# 03-MCU.net
KiCad netlist of a schematic drawn in Altium Designer
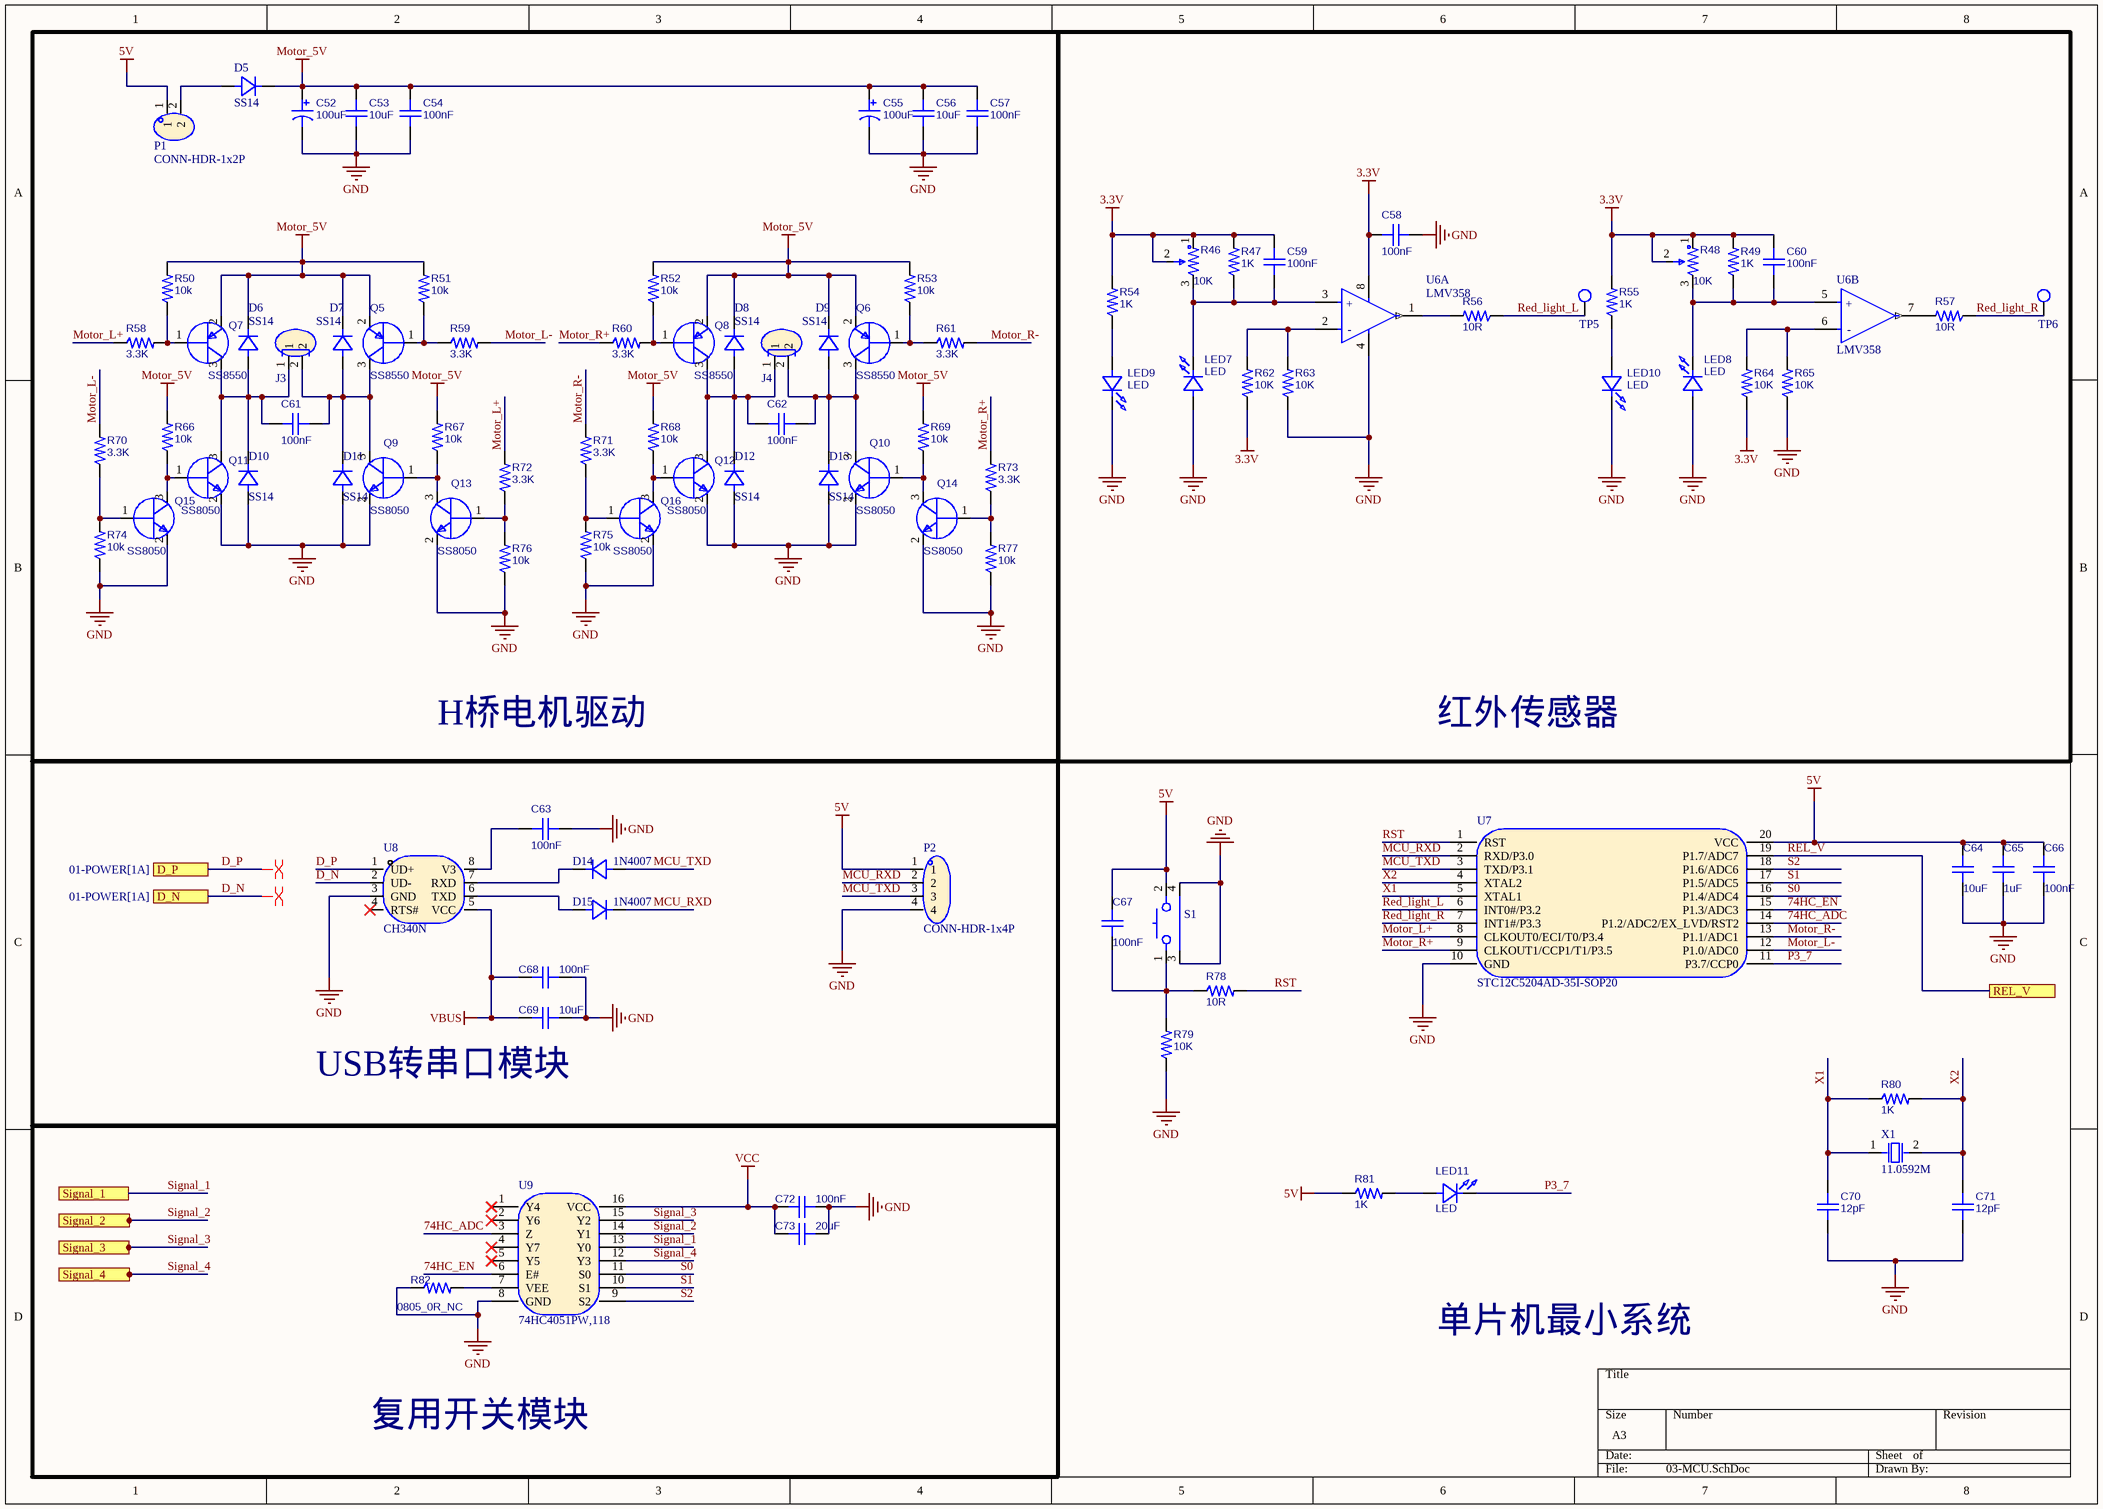
[diagram p0: 03-MCU.SchDoc]

(export (version "E")
  (design (tool "Eeschema 10.0.6"))
  (components
    (comp (ref "C52")
      (value "100uF")
      (footprint "CAPA-TH-5020-P2.0")
      (description "电解电容")
      (fields
        (field (name "BOM_MANUFACTURER PART") "普通黑色470UF 50V")
        (field (name "BOM_SUPPLIER PART") "C34642")
      )
      (libsource (lib "声源跟踪小车原理图库") (part "CAPA"))
    )
    (comp (ref "C53")
      (value "10uF")
      (footprint "CAP-SMD-0603")
      (description "贴片电容")
      (fields
        (field (name "BOM_MANUFACTURER PART") "CL03A104KQ3NNNC")
        (field (name "BOM_SUPPLIER PART") "C160831")
        (field (name "CONTRIBUTOR") "LCSC")
      )
      (libsource (lib "声源跟踪小车原理图库") (part "CAP"))
    )
    (comp (ref "C54")
      (value "100nF")
      (footprint "CAP-SMD-0603")
      (description "贴片电容")
      (fields
        (field (name "BOM_MANUFACTURER PART") "CL03A104KQ3NNNC")
        (field (name "BOM_SUPPLIER PART") "C160831")
        (field (name "CONTRIBUTOR") "LCSC")
      )
      (libsource (lib "声源跟踪小车原理图库") (part "CAP"))
    )
    (comp (ref "C55")
      (value "100uF")
      (footprint "CAPA-TH-5020-P2.0")
      (description "电解电容")
      (fields
        (field (name "BOM_MANUFACTURER PART") "普通黑色470UF 50V")
        (field (name "BOM_SUPPLIER PART") "C34642")
      )
      (libsource (lib "声源跟踪小车原理图库") (part "CAPA"))
    )
    (comp (ref "C56")
      (value "10uF")
      (footprint "CAP-SMD-0603")
      (description "贴片电容")
      (fields
        (field (name "BOM_MANUFACTURER PART") "CL03A104KQ3NNNC")
        (field (name "BOM_SUPPLIER PART") "C160831")
        (field (name "CONTRIBUTOR") "LCSC")
      )
      (libsource (lib "声源跟踪小车原理图库") (part "CAP"))
    )
    (comp (ref "C57")
      (value "100nF")
      (footprint "CAP-SMD-0603")
      (description "贴片电容")
      (fields
        (field (name "BOM_MANUFACTURER PART") "CL03A104KQ3NNNC")
        (field (name "BOM_SUPPLIER PART") "C160831")
        (field (name "CONTRIBUTOR") "LCSC")
      )
      (libsource (lib "声源跟踪小车原理图库") (part "CAP"))
    )
    (comp (ref "C58")
      (value "100nF")
      (footprint "CAP-SMD-0603")
      (description "贴片电容")
      (fields
        (field (name "BOM_MANUFACTURER PART") "CL03A104KQ3NNNC")
        (field (name "BOM_SUPPLIER PART") "C160831")
        (field (name "CONTRIBUTOR") "LCSC")
      )
      (libsource (lib "声源跟踪小车原理图库") (part "CAP"))
    )
    (comp (ref "C59")
      (value "100nF")
      (footprint "CAP-SMD-0603")
      (description "贴片电容")
      (fields
        (field (name "BOM_MANUFACTURER PART") "CL03A104KQ3NNNC")
        (field (name "BOM_SUPPLIER PART") "C160831")
        (field (name "CONTRIBUTOR") "LCSC")
      )
      (libsource (lib "声源跟踪小车原理图库") (part "CAP"))
    )
    (comp (ref "C60")
      (value "100nF")
      (footprint "CAP-SMD-0603")
      (description "贴片电容")
      (fields
        (field (name "BOM_MANUFACTURER PART") "CL03A104KQ3NNNC")
        (field (name "BOM_SUPPLIER PART") "C160831")
        (field (name "CONTRIBUTOR") "LCSC")
      )
      (libsource (lib "声源跟踪小车原理图库") (part "CAP"))
    )
    (comp (ref "C61")
      (value "100nF")
      (footprint "CAP-SMD-0603")
      (description "贴片电容")
      (fields
        (field (name "BOM_MANUFACTURER PART") "CL03A104KQ3NNNC")
        (field (name "BOM_SUPPLIER PART") "C160831")
        (field (name "CONTRIBUTOR") "LCSC")
      )
      (libsource (lib "声源跟踪小车原理图库") (part "CAP"))
    )
    (comp (ref "C62")
      (value "100nF")
      (footprint "CAP-SMD-0603")
      (description "贴片电容")
      (fields
        (field (name "BOM_MANUFACTURER PART") "CL03A104KQ3NNNC")
        (field (name "BOM_SUPPLIER PART") "C160831")
        (field (name "CONTRIBUTOR") "LCSC")
      )
      (libsource (lib "声源跟踪小车原理图库") (part "CAP"))
    )
    (comp (ref "C63")
      (value "100nF")
      (footprint "CAP-SMD-0603")
      (description "贴片电容")
      (fields
        (field (name "BOM_MANUFACTURER PART") "CL03A104KQ3NNNC")
        (field (name "BOM_SUPPLIER PART") "C160831")
        (field (name "CONTRIBUTOR") "LCSC")
      )
      (libsource (lib "声源跟踪小车原理图库") (part "CAP"))
    )
    (comp (ref "C64")
      (value "10uF")
      (footprint "CAP-SMD-0603")
      (description "贴片电容")
      (fields
        (field (name "BOM_MANUFACTURER PART") "CL03A104KQ3NNNC")
        (field (name "BOM_SUPPLIER PART") "C160831")
        (field (name "CONTRIBUTOR") "LCSC")
      )
      (libsource (lib "声源跟踪小车原理图库") (part "CAP"))
    )
    (comp (ref "C65")
      (value "1uF")
      (footprint "CAP-SMD-0603")
      (description "贴片电容")
      (fields
        (field (name "BOM_MANUFACTURER PART") "CL03A104KQ3NNNC")
        (field (name "BOM_SUPPLIER PART") "C160831")
        (field (name "CONTRIBUTOR") "LCSC")
      )
      (libsource (lib "声源跟踪小车原理图库") (part "CAP"))
    )
    (comp (ref "C66")
      (value "100nF")
      (footprint "CAP-SMD-0603")
      (description "贴片电容")
      (fields
        (field (name "BOM_MANUFACTURER PART") "CL03A104KQ3NNNC")
        (field (name "BOM_SUPPLIER PART") "C160831")
        (field (name "CONTRIBUTOR") "LCSC")
      )
      (libsource (lib "声源跟踪小车原理图库") (part "CAP"))
    )
    (comp (ref "C67")
      (value "100nF")
      (footprint "CAP-SMD-0603")
      (description "贴片电容")
      (fields
        (field (name "BOM_MANUFACTURER PART") "CL03A104KQ3NNNC")
        (field (name "BOM_SUPPLIER PART") "C160831")
        (field (name "CONTRIBUTOR") "LCSC")
      )
      (libsource (lib "声源跟踪小车原理图库") (part "CAP"))
    )
    (comp (ref "C68")
      (value "100nF")
      (footprint "CAP-SMD-0603")
      (description "贴片电容")
      (fields
        (field (name "BOM_MANUFACTURER PART") "CL03A104KQ3NNNC")
        (field (name "BOM_SUPPLIER PART") "C160831")
        (field (name "CONTRIBUTOR") "LCSC")
      )
      (libsource (lib "声源跟踪小车原理图库") (part "CAP"))
    )
    (comp (ref "C69")
      (value "10uF")
      (footprint "CAP-SMD-0603")
      (description "贴片电容")
      (fields
        (field (name "BOM_MANUFACTURER PART") "CL03A104KQ3NNNC")
        (field (name "BOM_SUPPLIER PART") "C160831")
        (field (name "CONTRIBUTOR") "LCSC")
      )
      (libsource (lib "声源跟踪小车原理图库") (part "CAP"))
    )
    (comp (ref "C70")
      (value "12pF")
      (footprint "CAP-SMD-0603")
      (description "贴片电容")
      (fields
        (field (name "BOM_MANUFACTURER PART") "CL03A104KQ3NNNC")
        (field (name "BOM_SUPPLIER PART") "C160831")
        (field (name "CONTRIBUTOR") "LCSC")
      )
      (libsource (lib "声源跟踪小车原理图库") (part "CAP"))
    )
    (comp (ref "C71")
      (value "12pF")
      (footprint "CAP-SMD-0603")
      (description "贴片电容")
      (fields
        (field (name "BOM_MANUFACTURER PART") "CL03A104KQ3NNNC")
        (field (name "BOM_SUPPLIER PART") "C160831")
        (field (name "CONTRIBUTOR") "LCSC")
      )
      (libsource (lib "声源跟踪小车原理图库") (part "CAP"))
    )
    (comp (ref "C72")
      (value "100nF")
      (footprint "CAP-SMD-0603")
      (description "贴片电容")
      (fields
        (field (name "BOM_MANUFACTURER PART") "CL03A104KQ3NNNC")
        (field (name "BOM_SUPPLIER PART") "C160831")
        (field (name "CONTRIBUTOR") "LCSC")
      )
      (libsource (lib "声源跟踪小车原理图库") (part "CAP"))
    )
    (comp (ref "C73")
      (value "20uF")
      (footprint "CAP-SMD-0603")
      (description "贴片电容")
      (fields
        (field (name "BOM_MANUFACTURER PART") "CL03A104KQ3NNNC")
        (field (name "BOM_SUPPLIER PART") "C160831")
        (field (name "CONTRIBUTOR") "LCSC")
      )
      (libsource (lib "声源跟踪小车原理图库") (part "CAP"))
    )
    (comp (ref "D5")
      (value "SS14")
      (footprint "SOD-123-P3.4")
      (description "二极管1N4148W")
      (fields (field (name "MANUFACTURER") "PSI(宝力芯)") (field (name "MANUFACTURER PART") "1N4148W"))
      (libsource (lib "声源跟踪小车原理图库") (part "Diode"))
    )
    (comp (ref "D6")
      (value "SS14")
      (footprint "SOD-123-P3.4")
      (description "二极管1N4148W")
      (fields (field (name "MANUFACTURER") "PSI(宝力芯)") (field (name "MANUFACTURER PART") "1N4148W"))
      (libsource (lib "声源跟踪小车原理图库") (part "Diode"))
    )
    (comp (ref "D7")
      (value "SS14")
      (footprint "SOD-123-P3.4")
      (description "二极管1N4148W")
      (fields (field (name "MANUFACTURER") "PSI(宝力芯)") (field (name "MANUFACTURER PART") "1N4148W"))
      (libsource (lib "声源跟踪小车原理图库") (part "Diode"))
    )
    (comp (ref "D8")
      (value "SS14")
      (footprint "SOD-123-P3.4")
      (description "二极管1N4148W")
      (fields (field (name "MANUFACTURER") "PSI(宝力芯)") (field (name "MANUFACTURER PART") "1N4148W"))
      (libsource (lib "声源跟踪小车原理图库") (part "Diode"))
    )
    (comp (ref "D9")
      (value "SS14")
      (footprint "SOD-123-P3.4")
      (description "二极管1N4148W")
      (fields (field (name "MANUFACTURER") "PSI(宝力芯)") (field (name "MANUFACTURER PART") "1N4148W"))
      (libsource (lib "声源跟踪小车原理图库") (part "Diode"))
    )
    (comp (ref "D10")
      (value "SS14")
      (footprint "SOD-123-P3.4")
      (description "二极管1N4148W")
      (fields (field (name "MANUFACTURER") "PSI(宝力芯)") (field (name "MANUFACTURER PART") "1N4148W"))
      (libsource (lib "声源跟踪小车原理图库") (part "Diode"))
    )
    (comp (ref "D11")
      (value "SS14")
      (footprint "SOD-123-P3.4")
      (description "二极管1N4148W")
      (fields (field (name "MANUFACTURER") "PSI(宝力芯)") (field (name "MANUFACTURER PART") "1N4148W"))
      (libsource (lib "声源跟踪小车原理图库") (part "Diode"))
    )
    (comp (ref "D12")
      (value "SS14")
      (footprint "SOD-123-P3.4")
      (description "二极管1N4148W")
      (fields (field (name "MANUFACTURER") "PSI(宝力芯)") (field (name "MANUFACTURER PART") "1N4148W"))
      (libsource (lib "声源跟踪小车原理图库") (part "Diode"))
    )
    (comp (ref "D13")
      (value "SS14")
      (footprint "SOD-123-P3.4")
      (description "二极管1N4148W")
      (fields (field (name "MANUFACTURER") "PSI(宝力芯)") (field (name "MANUFACTURER PART") "1N4148W"))
      (libsource (lib "声源跟踪小车原理图库") (part "Diode"))
    )
    (comp (ref "D14")
      (value "1N4007")
      (footprint "SOD-123-P3.4")
      (description "二极管1N4148W")
      (fields (field (name "MANUFACTURER") "PSI(宝力芯)") (field (name "MANUFACTURER PART") "1N4148W"))
      (libsource (lib "声源跟踪小车原理图库") (part "Diode"))
    )
    (comp (ref "D15")
      (value "1N4007")
      (footprint "SOD-123-P3.4")
      (description "二极管1N4148W")
      (fields (field (name "MANUFACTURER") "PSI(宝力芯)") (field (name "MANUFACTURER PART") "1N4148W"))
      (libsource (lib "声源跟踪小车原理图库") (part "Diode"))
    )
    (comp (ref "J3")
      (value "CONN-2P")
      (footprint "CONN-TH-CDS-1x2P-P2.54")
      (description "连接插座2pin")
      (fields (field (name "MANUFACTURER") "KEFA(科发)") (field (name "MANUFACTURER PART") "KF301-5.0-2P"))
      (libsource (lib "声源跟踪小车原理图库") (part "CONN-2P"))
    )
    (comp (ref "J4")
      (value "CONN-2P")
      (footprint "CONN-TH-CDS-1x2P-P2.54")
      (description "连接插座2pin")
      (fields (field (name "MANUFACTURER") "KEFA(科发)") (field (name "MANUFACTURER PART") "KF301-5.0-2P"))
      (libsource (lib "声源跟踪小车原理图库") (part "CONN-2P"))
    )
    (comp (ref "LED7")
      (value "LED")
      (footprint "LED-TH-D5.0-P2.54")
      (description "LED灯,发光二极管")
      (fields
        (field (name "BOM_SUPPLIER PART") "C434447")
        (field (name "BOM_MANUFACTURER PART") "SZYY0402B")
        (field (name "CONTRIBUTOR") "LCSC")
      )
      (libsource (lib "声源跟踪小车原理图库") (part "LED"))
    )
    (comp (ref "LED8")
      (value "LED")
      (footprint "LED-TH-D5.0-P2.54")
      (description "LED灯,发光二极管")
      (fields
        (field (name "BOM_SUPPLIER PART") "C434447")
        (field (name "BOM_MANUFACTURER PART") "SZYY0402B")
        (field (name "CONTRIBUTOR") "LCSC")
      )
      (libsource (lib "声源跟踪小车原理图库") (part "LED"))
    )
    (comp (ref "LED9")
      (value "LED")
      (footprint "LED-TH-D5.0-P2.54")
      (description "LED灯,发光二极管")
      (fields
        (field (name "BOM_SUPPLIER PART") "C434447")
        (field (name "BOM_MANUFACTURER PART") "SZYY0402B")
        (field (name "CONTRIBUTOR") "LCSC")
      )
      (libsource (lib "声源跟踪小车原理图库") (part "LED"))
    )
    (comp (ref "LED10")
      (value "LED")
      (footprint "LED-TH-D5.0-P2.54")
      (description "LED灯,发光二极管")
      (fields
        (field (name "BOM_SUPPLIER PART") "C434447")
        (field (name "BOM_MANUFACTURER PART") "SZYY0402B")
        (field (name "CONTRIBUTOR") "LCSC")
      )
      (libsource (lib "声源跟踪小车原理图库") (part "LED"))
    )
    (comp (ref "LED11")
      (value "LED")
      (footprint "LED-SMD-0805")
      (description "LED灯,发光二极管")
      (fields
        (field (name "BOM_SUPPLIER PART") "C434447")
        (field (name "BOM_MANUFACTURER PART") "SZYY0402B")
        (field (name "CONTRIBUTOR") "LCSC")
      )
      (libsource (lib "声源跟踪小车原理图库") (part "LED"))
    )
    (comp (ref "P1")
      (value "CONN-HDR-1x2P")
      (footprint "CONN-TH-1X2P-P2.54")
      (description "排针1*2pin")
      (fields
        (field (name "MANUFACTURER") "kinghelm(金航标)")
        (field (name "MANUFACTURER PART") "KH-2.54PH180-1X2P-L11.5")
      )
      (libsource (lib "声源跟踪小车原理图库") (part "CONN-HDR-1x2P"))
    )
    (comp (ref "P2")
      (value "CONN-HDR-1x4P")
      (footprint "CONN-TH-1X4P-P2.54")
      (description "排针1*4pin")
      (fields
        (field (name "MANUFACTURER") "Wcon(维峰电子)")
        (field (name "MANUFACTURER PART") "1125-1104G0S116C001")
      )
      (libsource (lib "声源跟踪小车原理图库") (part "CONN-HDR-1x4P"))
    )
    (comp (ref "Q5")
      (value "SS8550")
      (footprint "SOT-23-3-LP2.28-P1.91")
      (description "贴片PNP三极管")
      (fields
        (field (name "BOM_SUPPLIER PART") "C2891799")
        (field (name "BOM_MANUFACTURER PART") "S9012")
        (field (name "CONTRIBUTOR") "LCSC")
      )
      (libsource (lib "声源跟踪小车原理图库") (part "PNP-SOT-23-3"))
    )
    (comp (ref "Q6")
      (value "SS8550")
      (footprint "SOT-23-3-LP2.28-P1.91")
      (description "贴片PNP三极管")
      (fields
        (field (name "BOM_SUPPLIER PART") "C2891799")
        (field (name "BOM_MANUFACTURER PART") "S9012")
        (field (name "CONTRIBUTOR") "LCSC")
      )
      (libsource (lib "声源跟踪小车原理图库") (part "PNP-SOT-23-3"))
    )
    (comp (ref "Q7")
      (value "SS8550")
      (footprint "SOT-23-3-LP2.28-P1.91")
      (description "贴片PNP三极管")
      (fields
        (field (name "BOM_SUPPLIER PART") "C2891799")
        (field (name "BOM_MANUFACTURER PART") "S9012")
        (field (name "CONTRIBUTOR") "LCSC")
      )
      (libsource (lib "声源跟踪小车原理图库") (part "PNP-SOT-23-3"))
    )
    (comp (ref "Q8")
      (value "SS8550")
      (footprint "SOT-23-3-LP2.28-P1.91")
      (description "贴片PNP三极管")
      (fields
        (field (name "BOM_SUPPLIER PART") "C2891799")
        (field (name "BOM_MANUFACTURER PART") "S9012")
        (field (name "CONTRIBUTOR") "LCSC")
      )
      (libsource (lib "声源跟踪小车原理图库") (part "PNP-SOT-23-3"))
    )
    (comp (ref "Q9")
      (value "SS8050")
      (footprint "SOT-23-3-LP2.28-P1.91")
      (description "贴片NPN三极管")
      (fields
        (field (name "BOM_SUPPLIER PART") "C2898668")
        (field (name "BOM_MANUFACTURER PART") "S9013")
        (field (name "CONTRIBUTOR") "LCSC")
      )
      (libsource (lib "声源跟踪小车原理图库") (part "NPN-SOT-23-3"))
    )
    (comp (ref "Q10")
      (value "SS8050")
      (footprint "SOT-23-3-LP2.28-P1.91")
      (description "贴片NPN三极管")
      (fields
        (field (name "BOM_SUPPLIER PART") "C2898668")
        (field (name "BOM_MANUFACTURER PART") "S9013")
        (field (name "CONTRIBUTOR") "LCSC")
      )
      (libsource (lib "声源跟踪小车原理图库") (part "NPN-SOT-23-3"))
    )
    (comp (ref "Q11")
      (value "SS8050")
      (footprint "SOT-23-3-LP2.28-P1.91")
      (description "贴片NPN三极管")
      (fields
        (field (name "BOM_SUPPLIER PART") "C2898668")
        (field (name "BOM_MANUFACTURER PART") "S9013")
        (field (name "CONTRIBUTOR") "LCSC")
      )
      (libsource (lib "声源跟踪小车原理图库") (part "NPN-SOT-23-3"))
    )
    (comp (ref "Q12")
      (value "SS8050")
      (footprint "SOT-23-3-LP2.28-P1.91")
      (description "贴片NPN三极管")
      (fields
        (field (name "BOM_SUPPLIER PART") "C2898668")
        (field (name "BOM_MANUFACTURER PART") "S9013")
        (field (name "CONTRIBUTOR") "LCSC")
      )
      (libsource (lib "声源跟踪小车原理图库") (part "NPN-SOT-23-3"))
    )
    (comp (ref "Q13")
      (value "SS8050")
      (footprint "SOT-23-3-LP2.28-P1.91")
      (description "贴片NPN三极管")
      (fields
        (field (name "BOM_SUPPLIER PART") "C2898668")
        (field (name "BOM_MANUFACTURER PART") "S9013")
        (field (name "CONTRIBUTOR") "LCSC")
      )
      (libsource (lib "声源跟踪小车原理图库") (part "NPN-SOT-23-3"))
    )
    (comp (ref "Q14")
      (value "SS8050")
      (footprint "SOT-23-3-LP2.28-P1.91")
      (description "贴片NPN三极管")
      (fields
        (field (name "BOM_SUPPLIER PART") "C2898668")
        (field (name "BOM_MANUFACTURER PART") "S9013")
        (field (name "CONTRIBUTOR") "LCSC")
      )
      (libsource (lib "声源跟踪小车原理图库") (part "NPN-SOT-23-3"))
    )
    (comp (ref "Q15")
      (value "SS8050")
      (footprint "SOT-23-3-LP2.28-P1.91")
      (description "贴片NPN三极管")
      (fields
        (field (name "BOM_SUPPLIER PART") "C2898668")
        (field (name "BOM_MANUFACTURER PART") "S9013")
        (field (name "CONTRIBUTOR") "LCSC")
      )
      (libsource (lib "声源跟踪小车原理图库") (part "NPN-SOT-23-3"))
    )
    (comp (ref "Q16")
      (value "SS8050")
      (footprint "SOT-23-3-LP2.28-P1.91")
      (description "贴片NPN三极管")
      (fields
        (field (name "BOM_SUPPLIER PART") "C2898668")
        (field (name "BOM_MANUFACTURER PART") "S9013")
        (field (name "CONTRIBUTOR") "LCSC")
      )
      (libsource (lib "声源跟踪小车原理图库") (part "NPN-SOT-23-3"))
    )
    (comp (ref "R46")
      (value "10K")
      (footprint "RES-TH-ADJ-3396W")
      (description "可调电阻,电位器")
      (fields
        (field (name "BOM_SUPPLIER PART") "C118966")
        (field (name "BOM_MANUFACTURER PART") "3362P-1-104")
        (field (name "CONTRIBUTOR") "LCSC")
      )
      (libsource (lib "声源跟踪小车原理图库") (part "RES-ADJ"))
    )
    (comp (ref "R47")
      (value "1K")
      (footprint "RES-SMD-0603")
      (description "贴片电阻")
      (fields
        (field (name "BOM_SUPPLIER PART") "C118966")
        (field (name "BOM_MANUFACTURER PART") "3362P-1-104")
        (field (name "CONTRIBUTOR") "LCSC")
      )
      (libsource (lib "声源跟踪小车原理图库") (part "RES"))
    )
    (comp (ref "R48")
      (value "10K")
      (footprint "RES-TH-ADJ-3396W")
      (description "可调电阻,电位器")
      (fields
        (field (name "BOM_SUPPLIER PART") "C118966")
        (field (name "BOM_MANUFACTURER PART") "3362P-1-104")
        (field (name "CONTRIBUTOR") "LCSC")
      )
      (libsource (lib "声源跟踪小车原理图库") (part "RES-ADJ"))
    )
    (comp (ref "R49")
      (value "1K")
      (footprint "RES-SMD-0603")
      (description "贴片电阻")
      (fields
        (field (name "BOM_SUPPLIER PART") "C118966")
        (field (name "BOM_MANUFACTURER PART") "3362P-1-104")
        (field (name "CONTRIBUTOR") "LCSC")
      )
      (libsource (lib "声源跟踪小车原理图库") (part "RES"))
    )
    (comp (ref "R50")
      (value "10k")
      (footprint "RES-SMD-0603")
      (description "贴片电阻")
      (fields
        (field (name "BOM_SUPPLIER PART") "C118966")
        (field (name "BOM_MANUFACTURER PART") "3362P-1-104")
        (field (name "CONTRIBUTOR") "LCSC")
      )
      (libsource (lib "声源跟踪小车原理图库") (part "RES"))
    )
    (comp (ref "R51")
      (value "10k")
      (footprint "RES-SMD-0603")
      (description "贴片电阻")
      (fields
        (field (name "BOM_SUPPLIER PART") "C118966")
        (field (name "BOM_MANUFACTURER PART") "3362P-1-104")
        (field (name "CONTRIBUTOR") "LCSC")
      )
      (libsource (lib "声源跟踪小车原理图库") (part "RES"))
    )
    (comp (ref "R52")
      (value "10k")
      (footprint "RES-SMD-0603")
      (description "贴片电阻")
      (fields
        (field (name "BOM_SUPPLIER PART") "C118966")
        (field (name "BOM_MANUFACTURER PART") "3362P-1-104")
        (field (name "CONTRIBUTOR") "LCSC")
      )
      (libsource (lib "声源跟踪小车原理图库") (part "RES"))
    )
    (comp (ref "R53")
      (value "10k")
      (footprint "RES-SMD-0603")
      (description "贴片电阻")
      (fields
        (field (name "BOM_SUPPLIER PART") "C118966")
        (field (name "BOM_MANUFACTURER PART") "3362P-1-104")
        (field (name "CONTRIBUTOR") "LCSC")
      )
      (libsource (lib "声源跟踪小车原理图库") (part "RES"))
    )
    (comp (ref "R54")
      (value "1K")
      (footprint "RES-SMD-0603")
      (description "贴片电阻")
      (fields
        (field (name "BOM_SUPPLIER PART") "C118966")
        (field (name "BOM_MANUFACTURER PART") "3362P-1-104")
        (field (name "CONTRIBUTOR") "LCSC")
      )
      (libsource (lib "声源跟踪小车原理图库") (part "RES"))
    )
    (comp (ref "R55")
      (value "1K")
      (footprint "RES-SMD-0603")
      (description "贴片电阻")
      (fields
        (field (name "BOM_SUPPLIER PART") "C118966")
        (field (name "BOM_MANUFACTURER PART") "3362P-1-104")
        (field (name "CONTRIBUTOR") "LCSC")
      )
      (libsource (lib "声源跟踪小车原理图库") (part "RES"))
    )
    (comp (ref "R56")
      (value "10R")
      (footprint "RES-SMD-0603")
      (description "贴片电阻")
      (fields
        (field (name "BOM_SUPPLIER PART") "C118966")
        (field (name "BOM_MANUFACTURER PART") "3362P-1-104")
        (field (name "CONTRIBUTOR") "LCSC")
      )
      (libsource (lib "声源跟踪小车原理图库") (part "RES"))
    )
    (comp (ref "R57")
      (value "10R")
      (footprint "RES-SMD-0603")
      (description "贴片电阻")
      (fields
        (field (name "BOM_SUPPLIER PART") "C118966")
        (field (name "BOM_MANUFACTURER PART") "3362P-1-104")
        (field (name "CONTRIBUTOR") "LCSC")
      )
      (libsource (lib "声源跟踪小车原理图库") (part "RES"))
    )
    (comp (ref "R58")
      (value "3.3K")
      (footprint "RES-SMD-0603")
      (description "贴片电阻")
      (fields
        (field (name "BOM_SUPPLIER PART") "C118966")
        (field (name "BOM_MANUFACTURER PART") "3362P-1-104")
        (field (name "CONTRIBUTOR") "LCSC")
      )
      (libsource (lib "声源跟踪小车原理图库") (part "RES"))
    )
    (comp (ref "R59")
      (value "3.3K")
      (footprint "RES-SMD-0603")
      (description "贴片电阻")
      (fields
        (field (name "BOM_SUPPLIER PART") "C118966")
        (field (name "BOM_MANUFACTURER PART") "3362P-1-104")
        (field (name "CONTRIBUTOR") "LCSC")
      )
      (libsource (lib "声源跟踪小车原理图库") (part "RES"))
    )
    (comp (ref "R60")
      (value "3.3K")
      (footprint "RES-SMD-0603")
      (description "贴片电阻")
      (fields
        (field (name "BOM_SUPPLIER PART") "C118966")
        (field (name "BOM_MANUFACTURER PART") "3362P-1-104")
        (field (name "CONTRIBUTOR") "LCSC")
      )
      (libsource (lib "声源跟踪小车原理图库") (part "RES"))
    )
    (comp (ref "R61")
      (value "3.3K")
      (footprint "RES-SMD-0603")
      (description "贴片电阻")
      (fields
        (field (name "BOM_SUPPLIER PART") "C118966")
        (field (name "BOM_MANUFACTURER PART") "3362P-1-104")
        (field (name "CONTRIBUTOR") "LCSC")
      )
      (libsource (lib "声源跟踪小车原理图库") (part "RES"))
    )
    (comp (ref "R62")
      (value "10K")
      (footprint "RES-SMD-0603")
      (description "贴片电阻")
      (fields
        (field (name "BOM_SUPPLIER PART") "C118966")
        (field (name "BOM_MANUFACTURER PART") "3362P-1-104")
        (field (name "CONTRIBUTOR") "LCSC")
      )
      (libsource (lib "声源跟踪小车原理图库") (part "RES"))
    )
    (comp (ref "R63")
      (value "10K")
      (footprint "RES-SMD-0603")
      (description "贴片电阻")
      (fields
        (field (name "BOM_SUPPLIER PART") "C118966")
        (field (name "BOM_MANUFACTURER PART") "3362P-1-104")
        (field (name "CONTRIBUTOR") "LCSC")
      )
      (libsource (lib "声源跟踪小车原理图库") (part "RES"))
    )
    (comp (ref "R64")
      (value "10K")
      (footprint "RES-SMD-0603")
      (description "贴片电阻")
      (fields
        (field (name "BOM_SUPPLIER PART") "C118966")
        (field (name "BOM_MANUFACTURER PART") "3362P-1-104")
        (field (name "CONTRIBUTOR") "LCSC")
      )
      (libsource (lib "声源跟踪小车原理图库") (part "RES"))
    )
    (comp (ref "R65")
      (value "10K")
      (footprint "RES-SMD-0603")
      (description "贴片电阻")
      (fields
        (field (name "BOM_SUPPLIER PART") "C118966")
        (field (name "BOM_MANUFACTURER PART") "3362P-1-104")
        (field (name "CONTRIBUTOR") "LCSC")
      )
      (libsource (lib "声源跟踪小车原理图库") (part "RES"))
    )
    (comp (ref "R66")
      (value "10k")
      (footprint "RES-SMD-0603")
      (description "贴片电阻")
      (fields
        (field (name "BOM_SUPPLIER PART") "C118966")
        (field (name "BOM_MANUFACTURER PART") "3362P-1-104")
        (field (name "CONTRIBUTOR") "LCSC")
      )
      (libsource (lib "声源跟踪小车原理图库") (part "RES"))
    )
    (comp (ref "R67")
      (value "10k")
      (footprint "RES-SMD-0603")
      (description "贴片电阻")
      (fields
        (field (name "BOM_SUPPLIER PART") "C118966")
        (field (name "BOM_MANUFACTURER PART") "3362P-1-104")
        (field (name "CONTRIBUTOR") "LCSC")
      )
      (libsource (lib "声源跟踪小车原理图库") (part "RES"))
    )
    (comp (ref "R68")
      (value "10k")
      (footprint "RES-SMD-0603")
      (description "贴片电阻")
      (fields
        (field (name "BOM_SUPPLIER PART") "C118966")
        (field (name "BOM_MANUFACTURER PART") "3362P-1-104")
        (field (name "CONTRIBUTOR") "LCSC")
      )
      (libsource (lib "声源跟踪小车原理图库") (part "RES"))
    )
    (comp (ref "R69")
      (value "10k")
      (footprint "RES-SMD-0603")
      (description "贴片电阻")
      (fields
        (field (name "BOM_SUPPLIER PART") "C118966")
        (field (name "BOM_MANUFACTURER PART") "3362P-1-104")
        (field (name "CONTRIBUTOR") "LCSC")
      )
      (libsource (lib "声源跟踪小车原理图库") (part "RES"))
    )
    (comp (ref "R70")
      (value "3.3K")
      (footprint "RES-SMD-0603")
      (description "贴片电阻")
      (fields
        (field (name "BOM_SUPPLIER PART") "C118966")
        (field (name "BOM_MANUFACTURER PART") "3362P-1-104")
        (field (name "CONTRIBUTOR") "LCSC")
      )
      (libsource (lib "声源跟踪小车原理图库") (part "RES"))
    )
    (comp (ref "R71")
      (value "3.3K")
      (footprint "RES-SMD-0603")
      (description "贴片电阻")
      (fields
        (field (name "BOM_SUPPLIER PART") "C118966")
        (field (name "BOM_MANUFACTURER PART") "3362P-1-104")
        (field (name "CONTRIBUTOR") "LCSC")
      )
      (libsource (lib "声源跟踪小车原理图库") (part "RES"))
    )
    (comp (ref "R72")
      (value "3.3K")
      (footprint "RES-SMD-0603")
      (description "贴片电阻")
      (fields
        (field (name "BOM_SUPPLIER PART") "C118966")
        (field (name "BOM_MANUFACTURER PART") "3362P-1-104")
        (field (name "CONTRIBUTOR") "LCSC")
      )
      (libsource (lib "声源跟踪小车原理图库") (part "RES"))
    )
    (comp (ref "R73")
      (value "3.3K")
      (footprint "RES-SMD-0603")
      (description "贴片电阻")
      (fields
        (field (name "BOM_SUPPLIER PART") "C118966")
        (field (name "BOM_MANUFACTURER PART") "3362P-1-104")
        (field (name "CONTRIBUTOR") "LCSC")
      )
      (libsource (lib "声源跟踪小车原理图库") (part "RES"))
    )
    (comp (ref "R74")
      (value "10k")
      (footprint "RES-SMD-0603")
      (description "贴片电阻")
      (fields
        (field (name "BOM_SUPPLIER PART") "C118966")
        (field (name "BOM_MANUFACTURER PART") "3362P-1-104")
        (field (name "CONTRIBUTOR") "LCSC")
      )
      (libsource (lib "声源跟踪小车原理图库") (part "RES"))
    )
    (comp (ref "R75")
      (value "10k")
      (footprint "RES-SMD-0603")
      (description "贴片电阻")
      (fields
        (field (name "BOM_SUPPLIER PART") "C118966")
        (field (name "BOM_MANUFACTURER PART") "3362P-1-104")
        (field (name "CONTRIBUTOR") "LCSC")
      )
      (libsource (lib "声源跟踪小车原理图库") (part "RES"))
    )
    (comp (ref "R76")
      (value "10k")
      (footprint "RES-SMD-0603")
      (description "贴片电阻")
      (fields
        (field (name "BOM_SUPPLIER PART") "C118966")
        (field (name "BOM_MANUFACTURER PART") "3362P-1-104")
        (field (name "CONTRIBUTOR") "LCSC")
      )
      (libsource (lib "声源跟踪小车原理图库") (part "RES"))
    )
    (comp (ref "R77")
      (value "10k")
      (footprint "RES-SMD-0603")
      (description "贴片电阻")
      (fields
        (field (name "BOM_SUPPLIER PART") "C118966")
        (field (name "BOM_MANUFACTURER PART") "3362P-1-104")
        (field (name "CONTRIBUTOR") "LCSC")
      )
      (libsource (lib "声源跟踪小车原理图库") (part "RES"))
    )
    (comp (ref "R78")
      (value "10R")
      (footprint "RES-SMD-0603")
      (description "贴片电阻")
      (fields
        (field (name "BOM_SUPPLIER PART") "C118966")
        (field (name "BOM_MANUFACTURER PART") "3362P-1-104")
        (field (name "CONTRIBUTOR") "LCSC")
      )
      (libsource (lib "声源跟踪小车原理图库") (part "RES"))
    )
    (comp (ref "R79")
      (value "10K")
      (footprint "RES-SMD-0603")
      (description "贴片电阻")
      (fields
        (field (name "BOM_SUPPLIER PART") "C118966")
        (field (name "BOM_MANUFACTURER PART") "3362P-1-104")
        (field (name "CONTRIBUTOR") "LCSC")
      )
      (libsource (lib "声源跟踪小车原理图库") (part "RES"))
    )
    (comp (ref "R80")
      (value "1K")
      (footprint "RES-SMD-0603")
      (description "贴片电阻")
      (fields
        (field (name "BOM_SUPPLIER PART") "C118966")
        (field (name "BOM_MANUFACTURER PART") "3362P-1-104")
        (field (name "CONTRIBUTOR") "LCSC")
      )
      (libsource (lib "声源跟踪小车原理图库") (part "RES"))
    )
    (comp (ref "R81")
      (value "1K")
      (footprint "RES-SMD-0603")
      (description "贴片电阻")
      (fields
        (field (name "BOM_SUPPLIER PART") "C118966")
        (field (name "BOM_MANUFACTURER PART") "3362P-1-104")
        (field (name "CONTRIBUTOR") "LCSC")
      )
      (libsource (lib "声源跟踪小车原理图库") (part "RES"))
    )
    (comp (ref "R82")
      (value "0805_0R_NC")
      (footprint "RES-SMD-0603")
      (description "贴片电阻")
      (fields
        (field (name "BOM_SUPPLIER PART") "C118966")
        (field (name "BOM_MANUFACTURER PART") "3362P-1-104")
        (field (name "CONTRIBUTOR") "LCSC")
      )
      (libsource (lib "声源跟踪小车原理图库") (part "RES"))
    )
    (comp (ref "S1")
      (value "KEY-B-2P")
      (footprint "KEY-TH-B-2P")
      (description "按键开关B")
      (fields (field (name "MANUFACTURER") "C&K") (field (name "MANUFACTURER PART") "PTS645VL83LFS"))
      (libsource (lib "声源跟踪小车原理图库") (part "KEY-B-2P"))
    )
    (comp (ref "TP5")
      (value "TP")
      (footprint "TP")
      (description "TP测试点")
      (libsource (lib "声源跟踪小车原理图库") (part "TP"))
    )
    (comp (ref "TP6")
      (value "TP")
      (footprint "TP")
      (description "TP测试点")
      (libsource (lib "声源跟踪小车原理图库") (part "TP"))
    )
    (comp (ref "U6")
      (value "LMV358")
      (footprint "SOIC-8-LP5.5-P1.27")
      (description "运放IC OPAMP GP 2 CIRCUIT 8SOIC")
      (libsource (lib "声源跟踪小车原理图库") (part "LMV358"))
    )
    (comp (ref "U7")
      (value "STC12C5204AD-35I-SOP20")
      (footprint "SOP-20")
      (fields (field (name "MANUFACTURER") "STC(宏晶)"))
      (libsource (lib "声源跟踪小车原理图库") (part "STC12C5204AD-35I-SOP20"))
    )
    (comp (ref "U8")
      (value "CH340N")
      (footprint "SOP-8-LP5.3-P1.27")
      (fields (field (name "MANUFACTURER") "WCH(南京沁恒)"))
      (libsource (lib "声源跟踪小车原理图库") (part "CH340N"))
    )
    (comp (ref "U9")
      (value "74HC4051PW,118")
      (footprint "TSSOP-16-LP5.7-P0.65")
      (description "复用开关IC MUX/DEMUX 8X1")
      (fields (field (name "MANUFACTURER") "Nexperia(安世)"))
      (libsource (lib "声源跟踪小车原理图库") (part "74HC4051PW,118"))
    )
    (comp (ref "X1")
      (value "11.0592M")
      (footprint "OSC-5032-SMD-2P")
      (description "无源晶振2pin")
      (fields (field (name "MANUFACTURER") "YXC扬兴科技") (field (name "MANUFACTURER PART") "X49SM16MSD2SI"))
      (libsource (lib "声源跟踪小车原理图库") (part "XTAL-2P-WY"))
    )
  )
  (nets
    (net (code "1") (name "/74HC_ADC") (class "Default")
      (node (ref "U7") (pin "14") (pinfunction "P1.2/ADC2/EX_LVD/RST2_14") (pintype "passive"))
      (node (ref "U9") (pin "3") (pinfunction "Z_3") (pintype "passive"))
    )
    (net (code "2") (name "/74HC_EN") (class "Default")
      (node (ref "U7") (pin "15") (pinfunction "P1.3/ADC3_15") (pintype "passive"))
      (node (ref "U9") (pin "6") (pinfunction "E#_6") (pintype "passive"))
    )
    (net (code "3") (name "/D_N") (class "Default")
      (node (ref "U8") (pin "2") (pinfunction "UD-_2") (pintype "passive"))
    )
    (net (code "4") (name "/D_P") (class "Default")
      (node (ref "U8") (pin "1") (pinfunction "UD+_1") (pintype "passive"))
    )
    (net (code "5") (name "/MCU_RXD") (class "Default")
      (node (ref "D15") (pin "2") (pinfunction "A_2") (pintype "passive"))
      (node (ref "P2") (pin "2") (pinfunction "2_2") (pintype "passive"))
      (node (ref "U7") (pin "2") (pinfunction "RXD/P3.0_2") (pintype "passive"))
    )
    (net (code "6") (name "/MCU_TXD") (class "Default")
      (node (ref "D14") (pin "1") (pinfunction "K_1") (pintype "passive"))
      (node (ref "P2") (pin "3") (pinfunction "3_3") (pintype "passive"))
      (node (ref "U7") (pin "3") (pinfunction "TXD/P3.1_3") (pintype "passive"))
    )
    (net (code "7") (name "/Motor_L+") (class "Default")
      (node (ref "R58") (pin "1") (pinfunction "1_1") (pintype "passive"))
      (node (ref "R72") (pin "2") (pinfunction "2_2") (pintype "passive"))
      (node (ref "U7") (pin "8") (pinfunction "CLKOUT0/ECI/T0/P3.4_8") (pintype "passive"))
    )
    (net (code "8") (name "/Motor_L-") (class "Default")
      (node (ref "R59") (pin "2") (pinfunction "2_2") (pintype "passive"))
      (node (ref "R70") (pin "2") (pinfunction "2_2") (pintype "passive"))
      (node (ref "U7") (pin "12") (pinfunction "P1.0/ADC0_12") (pintype "passive"))
    )
    (net (code "9") (name "/Motor_R+") (class "Default")
      (node (ref "R60") (pin "1") (pinfunction "1_1") (pintype "passive"))
      (node (ref "R73") (pin "2") (pinfunction "2_2") (pintype "passive"))
      (node (ref "U7") (pin "9") (pinfunction "CLKOUT1/CCP1/T1/P3.5_9") (pintype "passive"))
    )
    (net (code "10") (name "/Motor_R-") (class "Default")
      (node (ref "R61") (pin "2") (pinfunction "2_2") (pintype "passive"))
      (node (ref "R71") (pin "2") (pinfunction "2_2") (pintype "passive"))
      (node (ref "U7") (pin "13") (pinfunction "P1.1/ADC1_13") (pintype "passive"))
    )
    (net (code "11") (name "/P3_7") (class "Default")
      (node (ref "LED11") (pin "2") (pinfunction "K_2") (pintype "passive"))
      (node (ref "U7") (pin "11") (pinfunction "P3.7/CCP0_11") (pintype "passive"))
    )
    (net (code "12") (name "/REL_V") (class "Default")
      (node (ref "U7") (pin "19") (pinfunction "P1.7/ADC7_19") (pintype "passive"))
    )
    (net (code "13") (name "/RST") (class "Default")
      (node (ref "R78") (pin "2") (pinfunction "2_2") (pintype "passive"))
      (node (ref "U7") (pin "1") (pinfunction "RST_1") (pintype "passive"))
    )
    (net (code "14") (name "/Red_light_L") (class "Default")
      (node (ref "R56") (pin "1") (pinfunction "1_1") (pintype "passive"))
      (node (ref "TP5") (pin "1") (pinfunction "1_1") (pintype "passive"))
      (node (ref "U7") (pin "6") (pinfunction "INT0#/P3.2_6") (pintype "passive"))
    )
    (net (code "15") (name "/Red_light_R") (class "Default")
      (node (ref "R57") (pin "1") (pinfunction "1_1") (pintype "passive"))
      (node (ref "TP6") (pin "1") (pinfunction "1_1") (pintype "passive"))
      (node (ref "U7") (pin "7") (pinfunction "INT1#/P3.3_7") (pintype "passive"))
    )
    (net (code "16") (name "/S0") (class "Default")
      (node (ref "U7") (pin "16") (pinfunction "P1.4/ADC4_16") (pintype "passive"))
      (node (ref "U9") (pin "11") (pinfunction "S0_11") (pintype "passive"))
    )
    (net (code "17") (name "/S1") (class "Default")
      (node (ref "U7") (pin "17") (pinfunction "P1.5/ADC5_17") (pintype "passive"))
      (node (ref "U9") (pin "10") (pinfunction "S1_10") (pintype "passive"))
    )
    (net (code "18") (name "/S2") (class "Default")
      (node (ref "U7") (pin "18") (pinfunction "P1.6/ADC6_18") (pintype "passive"))
      (node (ref "U9") (pin "9") (pinfunction "S2_9") (pintype "passive"))
    )
    (net (code "19") (name "/Signal_1") (class "Default")
      (node (ref "U9") (pin "13") (pinfunction "Y0_13") (pintype "passive"))
    )
    (net (code "20") (name "/Signal_2") (class "Default")
      (node (ref "U9") (pin "14") (pinfunction "Y1_14") (pintype "passive"))
    )
    (net (code "21") (name "/Signal_3") (class "Default")
      (node (ref "U9") (pin "15") (pinfunction "Y2_15") (pintype "passive"))
    )
    (net (code "22") (name "/Signal_4") (class "Default")
      (node (ref "U9") (pin "12") (pinfunction "Y3_12") (pintype "passive"))
    )
    (net (code "23") (name "/X1") (class "Default")
      (node (ref "C70") (pin "2") (pinfunction "2_2") (pintype "passive"))
      (node (ref "R80") (pin "1") (pinfunction "1_1") (pintype "passive"))
      (node (ref "U7") (pin "5") (pinfunction "XTAL1_5") (pintype "passive"))
      (node (ref "X1") (pin "1") (pinfunction "OSC1_1") (pintype "passive"))
    )
    (net (code "24") (name "/X2") (class "Default")
      (node (ref "C71") (pin "2") (pinfunction "2_2") (pintype "passive"))
      (node (ref "R80") (pin "2") (pinfunction "2_2") (pintype "passive"))
      (node (ref "U7") (pin "4") (pinfunction "XTAL2_4") (pintype "passive"))
      (node (ref "X1") (pin "2") (pinfunction "OSC2_2") (pintype "passive"))
    )
    (net (code "25") (name "3.3V") (class "Default")
      (node (ref "C58") (pin "2") (pinfunction "2_2") (pintype "passive"))
      (node (ref "C59") (pin "2") (pinfunction "2_2") (pintype "passive"))
      (node (ref "C60") (pin "2") (pinfunction "2_2") (pintype "passive"))
      (node (ref "R46") (pin "1") (pinfunction "1_1") (pintype "passive"))
      (node (ref "R46") (pin "2") (pinfunction "2_2") (pintype "passive"))
      (node (ref "R47") (pin "2") (pinfunction "2_2") (pintype "passive"))
      (node (ref "R48") (pin "1") (pinfunction "1_1") (pintype "passive"))
      (node (ref "R48") (pin "2") (pinfunction "2_2") (pintype "passive"))
      (node (ref "R49") (pin "2") (pinfunction "2_2") (pintype "passive"))
      (node (ref "R54") (pin "2") (pinfunction "2_2") (pintype "passive"))
      (node (ref "R55") (pin "2") (pinfunction "2_2") (pintype "passive"))
      (node (ref "R62") (pin "1") (pinfunction "1_1") (pintype "passive"))
      (node (ref "R64") (pin "1") (pinfunction "1_1") (pintype "passive"))
      (node (ref "U6") (pin "8") (pinfunction "VCC+_8") (pintype "power_in"))
    )
    (net (code "26") (name "5V") (class "Default")
      (node (ref "C64") (pin "2") (pinfunction "2_2") (pintype "passive"))
      (node (ref "C65") (pin "2") (pinfunction "2_2") (pintype "passive"))
      (node (ref "C66") (pin "2") (pinfunction "2_2") (pintype "passive"))
      (node (ref "C67") (pin "2") (pinfunction "2_2") (pintype "passive"))
      (node (ref "P1") (pin "1") (pinfunction "1_1") (pintype "passive"))
      (node (ref "P2") (pin "1") (pinfunction "1_1") (pintype "passive"))
      (node (ref "R81") (pin "1") (pinfunction "1_1") (pintype "passive"))
      (node (ref "S1") (pin "2") (pinfunction "2_2") (pintype "passive"))
      (node (ref "U7") (pin "20") (pinfunction "VCC_20") (pintype "passive"))
    )
    (net (code "27") (name "GND") (class "Default")
      (node (ref "C52") (pin "2") (pinfunction "2_2") (pintype "passive"))
      (node (ref "C53") (pin "1") (pinfunction "1_1") (pintype "passive"))
      (node (ref "C54") (pin "1") (pinfunction "1_1") (pintype "passive"))
      (node (ref "C55") (pin "2") (pinfunction "2_2") (pintype "passive"))
      (node (ref "C56") (pin "1") (pinfunction "1_1") (pintype "passive"))
      (node (ref "C57") (pin "1") (pinfunction "1_1") (pintype "passive"))
      (node (ref "C58") (pin "1") (pinfunction "1_1") (pintype "passive"))
      (node (ref "C63") (pin "2") (pinfunction "2_2") (pintype "passive"))
      (node (ref "C64") (pin "1") (pinfunction "1_1") (pintype "passive"))
      (node (ref "C65") (pin "1") (pinfunction "1_1") (pintype "passive"))
      (node (ref "C66") (pin "1") (pinfunction "1_1") (pintype "passive"))
      (node (ref "C68") (pin "2") (pinfunction "2_2") (pintype "passive"))
      (node (ref "C69") (pin "2") (pinfunction "2_2") (pintype "passive"))
      (node (ref "C70") (pin "1") (pinfunction "1_1") (pintype "passive"))
      (node (ref "C71") (pin "1") (pinfunction "1_1") (pintype "passive"))
      (node (ref "C72") (pin "2") (pinfunction "2_2") (pintype "passive"))
      (node (ref "C73") (pin "2") (pinfunction "2_2") (pintype "passive"))
      (node (ref "D10") (pin "1") (pinfunction "K_1") (pintype "passive"))
      (node (ref "D11") (pin "1") (pinfunction "K_1") (pintype "passive"))
      (node (ref "D12") (pin "1") (pinfunction "K_1") (pintype "passive"))
      (node (ref "D13") (pin "1") (pinfunction "K_1") (pintype "passive"))
      (node (ref "LED10") (pin "2") (pinfunction "K_2") (pintype "passive"))
      (node (ref "LED7") (pin "1") (pinfunction "A_1") (pintype "passive"))
      (node (ref "LED8") (pin "1") (pinfunction "A_1") (pintype "passive"))
      (node (ref "LED9") (pin "2") (pinfunction "K_2") (pintype "passive"))
      (node (ref "P2") (pin "4") (pinfunction "4_4") (pintype "passive"))
      (node (ref "Q10") (pin "2") (pinfunction "E_2") (pintype "passive"))
      (node (ref "Q11") (pin "2") (pinfunction "E_2") (pintype "passive"))
      (node (ref "Q12") (pin "2") (pinfunction "E_2") (pintype "passive"))
      (node (ref "Q13") (pin "2") (pinfunction "E_2") (pintype "passive"))
      (node (ref "Q14") (pin "2") (pinfunction "E_2") (pintype "passive"))
      (node (ref "Q15") (pin "2") (pinfunction "E_2") (pintype "passive"))
      (node (ref "Q16") (pin "2") (pinfunction "E_2") (pintype "passive"))
      (node (ref "Q9") (pin "2") (pinfunction "E_2") (pintype "passive"))
      (node (ref "R63") (pin "1") (pinfunction "1_1") (pintype "passive"))
      (node (ref "R65") (pin "1") (pinfunction "1_1") (pintype "passive"))
      (node (ref "R74") (pin "1") (pinfunction "1_1") (pintype "passive"))
      (node (ref "R75") (pin "1") (pinfunction "1_1") (pintype "passive"))
      (node (ref "R76") (pin "1") (pinfunction "1_1") (pintype "passive"))
      (node (ref "R77") (pin "1") (pinfunction "1_1") (pintype "passive"))
      (node (ref "R79") (pin "1") (pinfunction "1_1") (pintype "passive"))
      (node (ref "R82") (pin "1") (pinfunction "1_1") (pintype "passive"))
      (node (ref "S1") (pin "3") (pinfunction "3_3") (pintype "passive"))
      (node (ref "S1") (pin "4") (pinfunction "4_4") (pintype "passive"))
      (node (ref "U6") (pin "4") (pinfunction "GND_4") (pintype "power_in"))
      (node (ref "U7") (pin "10") (pinfunction "GND_10") (pintype "passive"))
      (node (ref "U8") (pin "3") (pinfunction "GND_3") (pintype "passive"))
      (node (ref "U9") (pin "8") (pinfunction "GND_8") (pintype "passive"))
    )
    (net (code "28") (name "Motor_5V") (class "Default")
      (node (ref "C52") (pin "1") (pinfunction "1_1") (pintype "passive"))
      (node (ref "C53") (pin "2") (pinfunction "2_2") (pintype "passive"))
      (node (ref "C54") (pin "2") (pinfunction "2_2") (pintype "passive"))
      (node (ref "C55") (pin "1") (pinfunction "1_1") (pintype "passive"))
      (node (ref "C56") (pin "2") (pinfunction "2_2") (pintype "passive"))
      (node (ref "C57") (pin "2") (pinfunction "2_2") (pintype "passive"))
      (node (ref "D5") (pin "2") (pinfunction "A_2") (pintype "passive"))
      (node (ref "D6") (pin "2") (pinfunction "A_2") (pintype "passive"))
      (node (ref "D7") (pin "2") (pinfunction "A_2") (pintype "passive"))
      (node (ref "D8") (pin "2") (pinfunction "A_2") (pintype "passive"))
      (node (ref "D9") (pin "2") (pinfunction "A_2") (pintype "passive"))
      (node (ref "Q5") (pin "2") (pinfunction "E_2") (pintype "passive"))
      (node (ref "Q6") (pin "2") (pinfunction "E_2") (pintype "passive"))
      (node (ref "Q7") (pin "2") (pinfunction "E_2") (pintype "passive"))
      (node (ref "Q8") (pin "2") (pinfunction "E_2") (pintype "passive"))
      (node (ref "R50") (pin "2") (pinfunction "2_2") (pintype "passive"))
      (node (ref "R51") (pin "2") (pinfunction "2_2") (pintype "passive"))
      (node (ref "R52") (pin "2") (pinfunction "2_2") (pintype "passive"))
      (node (ref "R53") (pin "2") (pinfunction "2_2") (pintype "passive"))
      (node (ref "R66") (pin "2") (pinfunction "2_2") (pintype "passive"))
      (node (ref "R67") (pin "2") (pinfunction "2_2") (pintype "passive"))
      (node (ref "R68") (pin "2") (pinfunction "2_2") (pintype "passive"))
      (node (ref "R69") (pin "2") (pinfunction "2_2") (pintype "passive"))
    )
    (net (code "29") (name "Net-(C67-Pad1)") (class "Default")
      (node (ref "C67") (pin "1") (pinfunction "1_1") (pintype "passive"))
      (node (ref "R78") (pin "1") (pinfunction "1_1") (pintype "passive"))
      (node (ref "R79") (pin "2") (pinfunction "2_2") (pintype "passive"))
      (node (ref "S1") (pin "1") (pinfunction "1_1") (pintype "passive"))
    )
    (net (code "30") (name "Net-(D5-K)") (class "Default")
      (node (ref "D5") (pin "1") (pinfunction "K_1") (pintype "passive"))
      (node (ref "P1") (pin "2") (pinfunction "2_2") (pintype "passive"))
    )
    (net (code "31") (name "Net-(D10-A)") (class "Default")
      (node (ref "C61") (pin "1") (pinfunction "1_1") (pintype "passive"))
      (node (ref "D10") (pin "2") (pinfunction "A_2") (pintype "passive"))
      (node (ref "D6") (pin "1") (pinfunction "K_1") (pintype "passive"))
      (node (ref "J3") (pin "1") (pinfunction "1_1") (pintype "passive"))
      (node (ref "Q11") (pin "3") (pinfunction "C_3") (pintype "passive"))
      (node (ref "Q7") (pin "3") (pinfunction "C_3") (pintype "passive"))
    )
    (net (code "32") (name "Net-(D11-A)") (class "Default")
      (node (ref "C61") (pin "2") (pinfunction "2_2") (pintype "passive"))
      (node (ref "D11") (pin "2") (pinfunction "A_2") (pintype "passive"))
      (node (ref "D7") (pin "1") (pinfunction "K_1") (pintype "passive"))
      (node (ref "J3") (pin "2") (pinfunction "2_2") (pintype "passive"))
      (node (ref "Q5") (pin "3") (pinfunction "C_3") (pintype "passive"))
      (node (ref "Q9") (pin "3") (pinfunction "C_3") (pintype "passive"))
    )
    (net (code "33") (name "Net-(D12-A)") (class "Default")
      (node (ref "C62") (pin "1") (pinfunction "1_1") (pintype "passive"))
      (node (ref "D12") (pin "2") (pinfunction "A_2") (pintype "passive"))
      (node (ref "D8") (pin "1") (pinfunction "K_1") (pintype "passive"))
      (node (ref "J4") (pin "1") (pinfunction "1_1") (pintype "passive"))
      (node (ref "Q12") (pin "3") (pinfunction "C_3") (pintype "passive"))
      (node (ref "Q8") (pin "3") (pinfunction "C_3") (pintype "passive"))
    )
    (net (code "34") (name "Net-(D13-A)") (class "Default")
      (node (ref "C62") (pin "2") (pinfunction "2_2") (pintype "passive"))
      (node (ref "D13") (pin "2") (pinfunction "A_2") (pintype "passive"))
      (node (ref "D9") (pin "1") (pinfunction "K_1") (pintype "passive"))
      (node (ref "J4") (pin "2") (pinfunction "2_2") (pintype "passive"))
      (node (ref "Q10") (pin "3") (pinfunction "C_3") (pintype "passive"))
      (node (ref "Q6") (pin "3") (pinfunction "C_3") (pintype "passive"))
    )
    (net (code "35") (name "Net-(D14-A)") (class "Default")
      (node (ref "D14") (pin "2") (pinfunction "A_2") (pintype "passive"))
      (node (ref "U8") (pin "7") (pinfunction "RXD_7") (pintype "passive"))
    )
    (net (code "36") (name "Net-(D15-K)") (class "Default")
      (node (ref "D15") (pin "1") (pinfunction "K_1") (pintype "passive"))
      (node (ref "U8") (pin "6") (pinfunction "TXD_6") (pintype "passive"))
    )
    (net (code "37") (name "Net-(LED7-K)") (class "Default")
      (node (ref "C59") (pin "1") (pinfunction "1_1") (pintype "passive"))
      (node (ref "LED7") (pin "2") (pinfunction "K_2") (pintype "passive"))
      (node (ref "R46") (pin "3") (pinfunction "3_3") (pintype "passive"))
      (node (ref "R47") (pin "1") (pinfunction "1_1") (pintype "passive"))
      (node (ref "U6") (pin "3") (pinfunction "1IN+_3") (pintype "tri_state"))
    )
    (net (code "38") (name "Net-(LED8-K)") (class "Default")
      (node (ref "C60") (pin "1") (pinfunction "1_1") (pintype "passive"))
      (node (ref "LED8") (pin "2") (pinfunction "K_2") (pintype "passive"))
      (node (ref "R48") (pin "3") (pinfunction "3_3") (pintype "passive"))
      (node (ref "R49") (pin "1") (pinfunction "1_1") (pintype "passive"))
      (node (ref "U6") (pin "5") (pinfunction "1IN+_5") (pintype "tri_state"))
    )
    (net (code "39") (name "Net-(LED9-A)") (class "Default")
      (node (ref "LED9") (pin "1") (pinfunction "A_1") (pintype "passive"))
      (node (ref "R54") (pin "1") (pinfunction "1_1") (pintype "passive"))
    )
    (net (code "40") (name "Net-(LED10-A)") (class "Default")
      (node (ref "LED10") (pin "1") (pinfunction "A_1") (pintype "passive"))
      (node (ref "R55") (pin "1") (pinfunction "1_1") (pintype "passive"))
    )
    (net (code "41") (name "Net-(LED11-A)") (class "Default")
      (node (ref "LED11") (pin "1") (pinfunction "A_1") (pintype "passive"))
      (node (ref "R81") (pin "2") (pinfunction "2_2") (pintype "passive"))
    )
    (net (code "42") (name "Net-(Q5-B)") (class "Default")
      (node (ref "Q5") (pin "1") (pinfunction "B_1") (pintype "passive"))
      (node (ref "R51") (pin "1") (pinfunction "1_1") (pintype "passive"))
      (node (ref "R59") (pin "1") (pinfunction "1_1") (pintype "passive"))
    )
    (net (code "43") (name "Net-(Q6-B)") (class "Default")
      (node (ref "Q6") (pin "1") (pinfunction "B_1") (pintype "passive"))
      (node (ref "R53") (pin "1") (pinfunction "1_1") (pintype "passive"))
      (node (ref "R61") (pin "1") (pinfunction "1_1") (pintype "passive"))
    )
    (net (code "44") (name "Net-(Q7-B)") (class "Default")
      (node (ref "Q7") (pin "1") (pinfunction "B_1") (pintype "passive"))
      (node (ref "R50") (pin "1") (pinfunction "1_1") (pintype "passive"))
      (node (ref "R58") (pin "2") (pinfunction "2_2") (pintype "passive"))
    )
    (net (code "45") (name "Net-(Q8-B)") (class "Default")
      (node (ref "Q8") (pin "1") (pinfunction "B_1") (pintype "passive"))
      (node (ref "R52") (pin "1") (pinfunction "1_1") (pintype "passive"))
      (node (ref "R60") (pin "2") (pinfunction "2_2") (pintype "passive"))
    )
    (net (code "46") (name "Net-(Q10-B)") (class "Default")
      (node (ref "Q10") (pin "1") (pinfunction "B_1") (pintype "passive"))
      (node (ref "Q14") (pin "3") (pinfunction "C_3") (pintype "passive"))
      (node (ref "R69") (pin "1") (pinfunction "1_1") (pintype "passive"))
    )
    (net (code "47") (name "Net-(Q11-B)") (class "Default")
      (node (ref "Q11") (pin "1") (pinfunction "B_1") (pintype "passive"))
      (node (ref "Q15") (pin "3") (pinfunction "C_3") (pintype "passive"))
      (node (ref "R66") (pin "1") (pinfunction "1_1") (pintype "passive"))
    )
    (net (code "48") (name "Net-(Q12-B)") (class "Default")
      (node (ref "Q12") (pin "1") (pinfunction "B_1") (pintype "passive"))
      (node (ref "Q16") (pin "3") (pinfunction "C_3") (pintype "passive"))
      (node (ref "R68") (pin "1") (pinfunction "1_1") (pintype "passive"))
    )
    (net (code "49") (name "Net-(Q13-B)") (class "Default")
      (node (ref "Q13") (pin "1") (pinfunction "B_1") (pintype "passive"))
      (node (ref "R72") (pin "1") (pinfunction "1_1") (pintype "passive"))
      (node (ref "R76") (pin "2") (pinfunction "2_2") (pintype "passive"))
    )
    (net (code "50") (name "Net-(Q13-C)") (class "Default")
      (node (ref "Q13") (pin "3") (pinfunction "C_3") (pintype "passive"))
      (node (ref "Q9") (pin "1") (pinfunction "B_1") (pintype "passive"))
      (node (ref "R67") (pin "1") (pinfunction "1_1") (pintype "passive"))
    )
    (net (code "51") (name "Net-(Q14-B)") (class "Default")
      (node (ref "Q14") (pin "1") (pinfunction "B_1") (pintype "passive"))
      (node (ref "R73") (pin "1") (pinfunction "1_1") (pintype "passive"))
      (node (ref "R77") (pin "2") (pinfunction "2_2") (pintype "passive"))
    )
    (net (code "52") (name "Net-(Q15-B)") (class "Default")
      (node (ref "Q15") (pin "1") (pinfunction "B_1") (pintype "passive"))
      (node (ref "R70") (pin "1") (pinfunction "1_1") (pintype "passive"))
      (node (ref "R74") (pin "2") (pinfunction "2_2") (pintype "passive"))
    )
    (net (code "53") (name "Net-(Q16-B)") (class "Default")
      (node (ref "Q16") (pin "1") (pinfunction "B_1") (pintype "passive"))
      (node (ref "R71") (pin "1") (pinfunction "1_1") (pintype "passive"))
      (node (ref "R75") (pin "2") (pinfunction "2_2") (pintype "passive"))
    )
    (net (code "54") (name "Net-(U6A-1IN-)") (class "Default")
      (node (ref "R62") (pin "2") (pinfunction "2_2") (pintype "passive"))
      (node (ref "R63") (pin "2") (pinfunction "2_2") (pintype "passive"))
      (node (ref "U6") (pin "2") (pinfunction "1IN-_2") (pintype "tri_state"))
    )
    (net (code "55") (name "Net-(U6A-OUT)") (class "Default")
      (node (ref "R56") (pin "2") (pinfunction "2_2") (pintype "passive"))
      (node (ref "U6") (pin "1") (pinfunction "OUT_1") (pintype "output"))
    )
    (net (code "56") (name "Net-(U6B-1IN-)") (class "Default")
      (node (ref "R64") (pin "2") (pinfunction "2_2") (pintype "passive"))
      (node (ref "R65") (pin "2") (pinfunction "2_2") (pintype "passive"))
      (node (ref "U6") (pin "6") (pinfunction "1IN-_6") (pintype "tri_state"))
    )
    (net (code "57") (name "Net-(U6B-OUT)") (class "Default")
      (node (ref "R57") (pin "2") (pinfunction "2_2") (pintype "passive"))
      (node (ref "U6") (pin "7") (pinfunction "OUT_7") (pintype "output"))
    )
    (net (code "58") (name "Net-(U8-V3)") (class "Default")
      (node (ref "C63") (pin "1") (pinfunction "1_1") (pintype "passive"))
      (node (ref "U8") (pin "8") (pinfunction "V3_8") (pintype "passive"))
    )
    (net (code "59") (name "Net-(U9-VEE)") (class "Default")
      (node (ref "R82") (pin "2") (pinfunction "2_2") (pintype "passive"))
      (node (ref "U9") (pin "7") (pinfunction "VEE_7") (pintype "passive"))
    )
    (net (code "60") (name "VBUS") (class "Default")
      (node (ref "C68") (pin "1") (pinfunction "1_1") (pintype "passive"))
      (node (ref "C69") (pin "1") (pinfunction "1_1") (pintype "passive"))
      (node (ref "U8") (pin "5") (pinfunction "VCC_5") (pintype "passive"))
    )
    (net (code "61") (name "VCC") (class "Default")
      (node (ref "C72") (pin "1") (pinfunction "1_1") (pintype "passive"))
      (node (ref "C73") (pin "1") (pinfunction "1_1") (pintype "passive"))
      (node (ref "U9") (pin "16") (pinfunction "VCC_16") (pintype "passive"))
    )
    (net (code "62") (name "unconnected-(U8-RTS#-Pad4)") (class "Default")
      (node (ref "U8") (pin "4") (pinfunction "RTS#_4") (pintype "passive+no_connect"))
    )
    (net (code "63") (name "unconnected-(U9-Y4-Pad1)") (class "Default")
      (node (ref "U9") (pin "1") (pinfunction "Y4_1") (pintype "passive+no_connect"))
    )
    (net (code "64") (name "unconnected-(U9-Y5-Pad5)") (class "Default")
      (node (ref "U9") (pin "5") (pinfunction "Y5_5") (pintype "passive+no_connect"))
    )
    (net (code "65") (name "unconnected-(U9-Y6-Pad2)") (class "Default")
      (node (ref "U9") (pin "2") (pinfunction "Y6_2") (pintype "passive+no_connect"))
    )
    (net (code "66") (name "unconnected-(U9-Y7-Pad4)") (class "Default")
      (node (ref "U9") (pin "4") (pinfunction "Y7_4") (pintype "passive+no_connect"))
    )
  )
)
